# CHECK2.net
KiCad netlist of a schematic drawn in Altium Designer
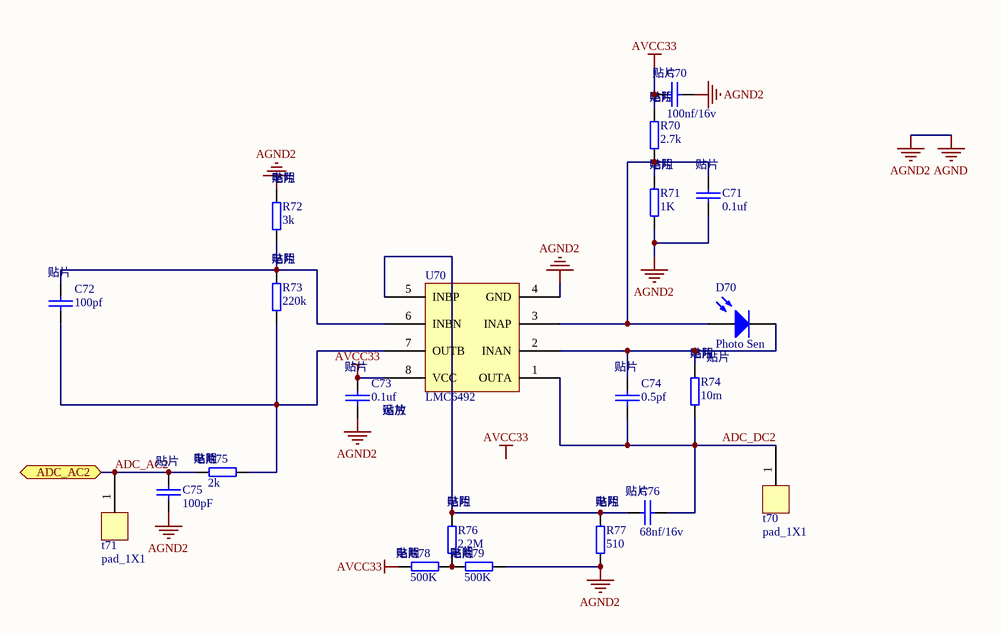
[diagram p0: CHECK2.SchDoc]

(export (version "E")
  (design (tool "Eeschema 10.0.6"))
  (components
    (comp (ref "C70")
      (value "100nf/16v")
      (footprint "C0402")
      (description "C")
      (libsource (lib "CxyDXP_SCH") (part "CC"))
    )
    (comp (ref "C71")
      (value "0.1uf")
      (footprint "C0402")
      (description "C")
      (libsource (lib "CxyDXP_SCH") (part "CC"))
    )
    (comp (ref "C72")
      (value "100pf")
      (footprint "C0402")
      (description "C")
      (libsource (lib "CxyDXP_SCH") (part "CC"))
    )
    (comp (ref "C73")
      (value "0.1uf")
      (footprint "C0402")
      (description "C")
      (libsource (lib "CxyDXP_SCH") (part "CC"))
    )
    (comp (ref "C74")
      (value "0.5pf")
      (footprint "C0402")
      (description "C")
      (libsource (lib "CxyDXP_SCH") (part "CC"))
    )
    (comp (ref "C75")
      (value "100pF")
      (footprint "C0402")
      (description "C")
      (libsource (lib "CxyDXP_SCH") (part "CC"))
    )
    (comp (ref "C76")
      (value "68nf/16v")
      (footprint "C0402")
      (description "C")
      (libsource (lib "CxyDXP_SCH") (part "CC"))
    )
    (comp (ref "D70")
      (value "Photo Sen")
      (footprint "PhotoSen")
      (description "Photosensitive Diode")
      (libsource (lib "Miscellaneous Devices") (part "Photo Sen"))
    )
    (comp (ref "R70")
      (value "2.7k")
      (footprint "R0402")
      (description "R")
      (libsource (lib "CxyDXP_SCH") (part "RES1"))
    )
    (comp (ref "R71")
      (value "1K")
      (footprint "R0402")
      (description "R")
      (libsource (lib "CxyDXP_SCH") (part "RES1"))
    )
    (comp (ref "R72")
      (value "3k")
      (footprint "R0402")
      (description "R")
      (libsource (lib "CxyDXP_SCH") (part "RES1"))
    )
    (comp (ref "R73")
      (value "220k")
      (footprint "R0402")
      (description "R")
      (libsource (lib "CxyDXP_SCH") (part "RES1"))
    )
    (comp (ref "R74")
      (value "10m")
      (footprint "R0402")
      (description "R")
      (libsource (lib "CxyDXP_SCH") (part "RES1"))
    )
    (comp (ref "R75")
      (value "2k")
      (footprint "R0402")
      (description "R")
      (libsource (lib "CxyDXP_SCH") (part "RES1"))
    )
    (comp (ref "R76")
      (value "2.2M")
      (footprint "R0402")
      (description "R")
      (libsource (lib "CxyDXP_SCH") (part "RES1"))
    )
    (comp (ref "R77")
      (value "510")
      (footprint "R0402")
      (description "R")
      (libsource (lib "CxyDXP_SCH") (part "RES1"))
    )
    (comp (ref "R78")
      (value "500K")
      (footprint "R0402")
      (description "R")
      (libsource (lib "CxyDXP_SCH") (part "RES1"))
    )
    (comp (ref "R79")
      (value "500K")
      (footprint "R0402")
      (description "R")
      (libsource (lib "CxyDXP_SCH") (part "RES1"))
    )
    (comp (ref "t70") (value "pad_1X1") (footprint "pad_0603") (libsource (lib "DUST") (part "pad_1X1")))
    (comp (ref "t71") (value "pad_1X1") (footprint "pad_0603") (libsource (lib "DUST") (part "pad_1X1")))
    (comp (ref "U70") (value "LMC6492") (footprint "SO-8") (libsource (lib "DUST") (part "LMC6492")))
  )
  (nets
    (net (code "1") (name "/ADC_AC2") (class "Default")
      (node (ref "C75") (pin "2") (pintype "passive"))
      (node (ref "R75") (pin "1") (pinfunction "1_1") (pintype "passive"))
      (node (ref "t71") (pin "1") (pintype "passive"))
    )
    (net (code "2") (name "/ADC_DC2") (class "Default")
      (node (ref "C74") (pin "2") (pintype "passive"))
      (node (ref "C76") (pin "2") (pintype "passive"))
      (node (ref "R74") (pin "2") (pinfunction "2_2") (pintype "passive"))
      (node (ref "U70") (pin "1") (pinfunction "OUTA_1") (pintype "passive"))
      (node (ref "t70") (pin "1") (pintype "passive"))
    )
    (net (code "3") (name "AGND") (class "Default")
      (node (ref "C70") (pin "2") (pintype "passive"))
      (node (ref "C71") (pin "2") (pintype "passive"))
      (node (ref "C73") (pin "2") (pintype "passive"))
      (node (ref "C75") (pin "1") (pintype "passive"))
      (node (ref "R71") (pin "2") (pinfunction "2_2") (pintype "passive"))
      (node (ref "R72") (pin "1") (pinfunction "1_1") (pintype "passive"))
      (node (ref "R77") (pin "2") (pinfunction "2_2") (pintype "passive"))
      (node (ref "R79") (pin "2") (pinfunction "2_2") (pintype "passive"))
      (node (ref "U70") (pin "4") (pinfunction "GND_4") (pintype "passive"))
    )
    (net (code "4") (name "AVCC33") (class "Default")
      (node (ref "C70") (pin "1") (pintype "passive"))
      (node (ref "C73") (pin "1") (pintype "passive"))
      (node (ref "R70") (pin "1") (pinfunction "1_1") (pintype "passive"))
      (node (ref "R78") (pin "1") (pinfunction "1_1") (pintype "passive"))
      (node (ref "U70") (pin "8") (pinfunction "VCC_8") (pintype "passive"))
    )
    (net (code "5") (name "Net-(D70-A)") (class "Default")
      (node (ref "C71") (pin "1") (pintype "passive"))
      (node (ref "D70") (pin "1") (pinfunction "A_1") (pintype "passive"))
      (node (ref "R70") (pin "2") (pinfunction "2_2") (pintype "passive"))
      (node (ref "R71") (pin "1") (pinfunction "1_1") (pintype "passive"))
      (node (ref "U70") (pin "3") (pinfunction "INAP_3") (pintype "passive"))
    )
    (net (code "6") (name "Net-(D70-K)") (class "Default")
      (node (ref "C74") (pin "1") (pintype "passive"))
      (node (ref "D70") (pin "2") (pinfunction "K_2") (pintype "passive"))
      (node (ref "R74") (pin "1") (pinfunction "1_1") (pintype "passive"))
      (node (ref "U70") (pin "2") (pinfunction "INAN_2") (pintype "passive"))
    )
    (net (code "7") (name "Net-(R76-Pad2)") (class "Default")
      (node (ref "R76") (pin "2") (pinfunction "2_2") (pintype "passive"))
      (node (ref "R78") (pin "2") (pinfunction "2_2") (pintype "passive"))
      (node (ref "R79") (pin "1") (pinfunction "1_1") (pintype "passive"))
    )
    (net (code "8") (name "Net-(U70-INBN)") (class "Default")
      (node (ref "C72") (pin "1") (pintype "passive"))
      (node (ref "R72") (pin "2") (pinfunction "2_2") (pintype "passive"))
      (node (ref "R73") (pin "1") (pinfunction "1_1") (pintype "passive"))
      (node (ref "U70") (pin "6") (pinfunction "INBN_6") (pintype "passive"))
    )
    (net (code "9") (name "Net-(U70-INBP)") (class "Default")
      (node (ref "C76") (pin "1") (pintype "passive"))
      (node (ref "R76") (pin "1") (pinfunction "1_1") (pintype "passive"))
      (node (ref "R77") (pin "1") (pinfunction "1_1") (pintype "passive"))
      (node (ref "U70") (pin "5") (pinfunction "INBP_5") (pintype "passive"))
    )
    (net (code "10") (name "Net-(U70-OUTB)") (class "Default")
      (node (ref "C72") (pin "2") (pintype "passive"))
      (node (ref "R73") (pin "2") (pinfunction "2_2") (pintype "passive"))
      (node (ref "R75") (pin "2") (pinfunction "2_2") (pintype "passive"))
      (node (ref "U70") (pin "7") (pinfunction "OUTB_7") (pintype "passive"))
    )
  )
)
